# 03_-_MODULE_BLE.net
KiCad netlist of a schematic drawn in Altium Designer
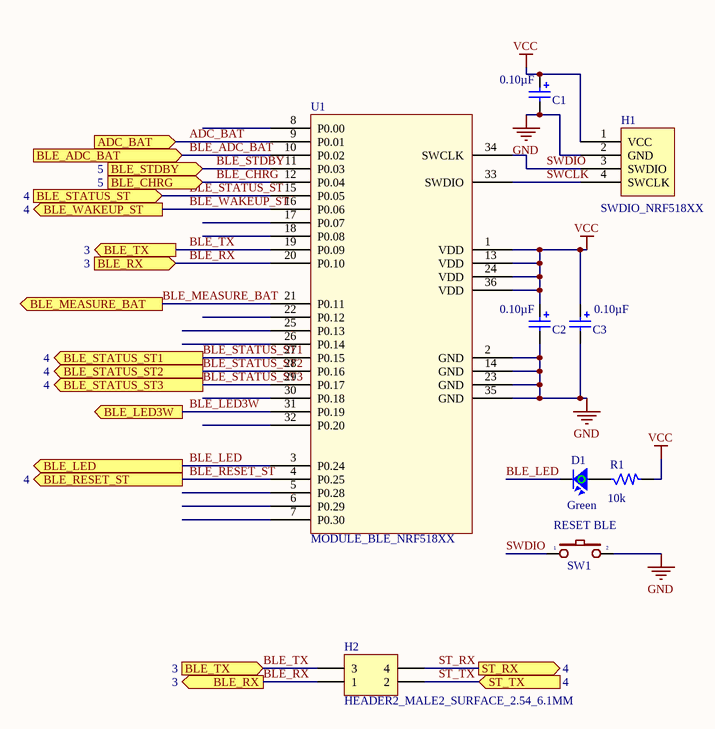
[diagram p0: [03] - MODULE BLE.SchDoc]

(export (version "E")
  (design (tool "Eeschema 10.0.6"))
  (components
    (comp (ref "C1")
      (value "C_104_0603_CERAMIC_16V")
      (footprint "CAP_SMD0603")
      (description "CAP CER 0.1UF 16V X7R 0603")
      (fields
        (field (name "MANUFACTURER") "Murata Electronics North America")
        (field (name "MANUFACTURER PART NUMBER") "GRM188R71C104KA01D")
        (field (name "CAPACITANCE") "0.10µF")
      )
      (libsource (lib "ALTIUM_LIB") (part "C_104_0603_CERAMIC_16V"))
    )
    (comp (ref "C2")
      (value "C_104_0603_CERAMIC_16V")
      (footprint "CAP_SMD0603")
      (description "CAP CER 0.1UF 16V X7R 0603")
      (fields
        (field (name "MANUFACTURER") "Murata Electronics North America")
        (field (name "MANUFACTURER PART NUMBER") "GRM188R71C104KA01D")
        (field (name "CAPACITANCE") "0.10µF")
      )
      (libsource (lib "ALTIUM_LIB") (part "C_104_0603_CERAMIC_16V"))
    )
    (comp (ref "C3")
      (value "C_104_0603_CERAMIC_16V")
      (footprint "CAP_SMD0603")
      (description "CAP CER 0.1UF 16V X7R 0603")
      (fields
        (field (name "MANUFACTURER") "Murata Electronics North America")
        (field (name "MANUFACTURER PART NUMBER") "GRM188R71C104KA01D")
        (field (name "CAPACITANCE") "0.10µF")
      )
      (libsource (lib "ALTIUM_LIB") (part "C_104_0603_CERAMIC_16V"))
    )
    (comp (ref "D1")
      (value "LED2_GREEN_0603_2V")
      (footprint "LED_GREEN_SMD0603")
      (description "LED GREEN CLEAR 0603 SMD")
      (fields
        (field (name "MANUFACTURER") "Lite-On Inc.")
        (field (name "MANUFACTURER PART NUMBER") "LTST-C191KGKT")
        (field (name "COLOR") "Green")
      )
      (libsource (lib "ALTIUM_LIB") (part "LED2_GREEN_0603_2V"))
    )
    (comp (ref "H1")
      (value "SWDIO_NRF518XX")
      (footprint "HEADER4_ISP_NRF518xx_SUR1.27")
      (description "CONN HEADER 4POS .100 STR TIN")
      (fields
        (field (name "MANUFACTURER") "Amphenol FCI")
        (field (name "MANUFACTURER PART NUMBER") "68002-404HLF")
      )
      (libsource (lib "ALTIUM_LIB") (part "HEADER4_ISP_NRF518XX_HOLE_2.54"))
    )
    (comp (ref "H2")
      (value "HEADER2_MALE2_SURFACE_2.54_6.1MM")
      (footprint "HEADER2_MALE2_SUR2.54")
      (description "CONN HEADER 4POS TIN SMD")
      (fields
        (field (name "MANUFACTURER") "Molex, LLC")
        (field (name "MANUFACTURER PART NUMBER") "0015912040")
      )
      (libsource (lib "SchematicLib") (part "HEADER2_MALE2_SURFACE_2.54_6.1MM"))
    )
    (comp (ref "R1")
      (value "R_10K_SMD0603_1%_1/10W")
      (footprint "RES_SMD0603")
      (description "RES SMD 10K OHM 1% 1/10W 0603")
      (fields
        (field (name "MANUFACTURER") "Yageo")
        (field (name "MANUFACTURER PART NUMBER") "RC0603FR-0710KL")
        (field (name "RESISTANCE (OHMS)") "10k")
      )
      (libsource (lib "ALTIUM_LIB") (part "R_10K_SMD0603_1%_1/10W"))
    )
    (comp (ref "SW1")
      (value "RESET BLE")
      (footprint "SW2-SMD")
      (description "SWITCH TACTILE SPST-NO 0.05A 12V")
      (fields
        (field (name "MANUFACTURER") "Wurth Electronics Inc")
        (field (name "MANUFACTURER PART NUMBER") "434121050836")
      )
      (libsource (lib "ALTIUM_LIB") (part "SW2_DPST_SURFACE_5MM"))
    )
    (comp (ref "U1")
      (value "MODULE_BLE_NRF518XX")
      (footprint "MODULE_NRF518xx")
      (libsource (lib "ALTIUM_LIB") (part "MODULE_BLE_NRF518XX"))
    )
  )
  (nets
    (net (code "1") (name "/ADC_BAT") (class "Default")
      (node (ref "U1") (pin "9") (pinfunction "P0.01_9") (pintype "passive"))
    )
    (net (code "2") (name "/BLE_ADC_BAT") (class "Default")
      (node (ref "U1") (pin "10") (pinfunction "P0.02_10") (pintype "passive"))
    )
    (net (code "3") (name "/BLE_CHRG") (class "Default")
      (node (ref "U1") (pin "12") (pinfunction "P0.04_12") (pintype "passive"))
    )
    (net (code "4") (name "/BLE_LED") (class "Default")
      (node (ref "D1") (pin "2") (pinfunction "2_2") (pintype "passive"))
      (node (ref "U1") (pin "3") (pinfunction "P0.24_3") (pintype "passive"))
    )
    (net (code "5") (name "/BLE_LED3W") (class "Default")
      (node (ref "U1") (pin "31") (pinfunction "P0.19_31") (pintype "passive"))
    )
    (net (code "6") (name "/BLE_MEASURE_BAT") (class "Default")
      (node (ref "U1") (pin "21") (pinfunction "P0.11_21") (pintype "passive"))
    )
    (net (code "7") (name "/BLE_RESET_ST") (class "Default")
      (node (ref "U1") (pin "4") (pinfunction "P0.25_4") (pintype "passive"))
    )
    (net (code "8") (name "/BLE_RX") (class "Default")
      (node (ref "H2") (pin "1") (pinfunction "1_1") (pintype "passive"))
      (node (ref "U1") (pin "20") (pinfunction "P0.10_20") (pintype "passive"))
    )
    (net (code "9") (name "/BLE_STATUS_ST") (class "Default")
      (node (ref "U1") (pin "15") (pinfunction "P0.05_15") (pintype "passive"))
    )
    (net (code "10") (name "/BLE_STATUS_ST1") (class "Default")
      (node (ref "U1") (pin "27") (pinfunction "P0.15_27") (pintype "passive"))
    )
    (net (code "11") (name "/BLE_STATUS_ST2") (class "Default")
      (node (ref "U1") (pin "28") (pinfunction "P0.16_28") (pintype "passive"))
    )
    (net (code "12") (name "/BLE_STATUS_ST3") (class "Default")
      (node (ref "U1") (pin "29") (pinfunction "P0.17_29") (pintype "passive"))
    )
    (net (code "13") (name "/BLE_STDBY") (class "Default")
      (node (ref "U1") (pin "11") (pinfunction "P0.03_11") (pintype "passive"))
    )
    (net (code "14") (name "/BLE_TX") (class "Default")
      (node (ref "H2") (pin "3") (pinfunction "3_3") (pintype "passive"))
      (node (ref "U1") (pin "19") (pinfunction "P0.09_19") (pintype "passive"))
    )
    (net (code "15") (name "/BLE_WAKEUP_ST") (class "Default")
      (node (ref "U1") (pin "16") (pinfunction "P0.06_16") (pintype "passive"))
    )
    (net (code "16") (name "/ST_RX") (class "Default")
      (node (ref "H2") (pin "4") (pinfunction "4_4") (pintype "passive"))
    )
    (net (code "17") (name "/ST_TX") (class "Default")
      (node (ref "H2") (pin "2") (pinfunction "2_2") (pintype "passive"))
    )
    (net (code "18") (name "/SWCLK") (class "Default")
      (node (ref "H1") (pin "4") (pinfunction "SWCLK_4") (pintype "passive"))
      (node (ref "U1") (pin "33") (pinfunction "SWDIO_33") (pintype "passive"))
    )
    (net (code "19") (name "/SWDIO") (class "Default")
      (node (ref "H1") (pin "3") (pinfunction "SWDIO_3") (pintype "passive"))
      (node (ref "SW1") (pin "1") (pinfunction "1_1") (pintype "passive"))
      (node (ref "U1") (pin "34") (pinfunction "SWCLK_34") (pintype "passive"))
    )
    (net (code "20") (name "GND") (class "Default")
      (node (ref "C1") (pin "2") (pinfunction "2_2") (pintype "passive"))
      (node (ref "C2") (pin "2") (pinfunction "2_2") (pintype "passive"))
      (node (ref "C3") (pin "2") (pinfunction "2_2") (pintype "passive"))
      (node (ref "H1") (pin "2") (pinfunction "GND_2") (pintype "passive"))
      (node (ref "SW1") (pin "2") (pinfunction "2_2") (pintype "passive"))
      (node (ref "U1") (pin "14") (pinfunction "GND_14") (pintype "passive"))
      (node (ref "U1") (pin "2") (pinfunction "GND_2") (pintype "passive"))
      (node (ref "U1") (pin "23") (pinfunction "GND_23") (pintype "passive"))
      (node (ref "U1") (pin "35") (pinfunction "GND_35") (pintype "passive"))
    )
    (net (code "21") (name "Net-(D1-Pad1)") (class "Default")
      (node (ref "D1") (pin "1") (pinfunction "1_1") (pintype "passive"))
      (node (ref "R1") (pin "1") (pinfunction "1_1") (pintype "passive"))
    )
    (net (code "22") (name "VCC") (class "Default")
      (node (ref "C1") (pin "1") (pinfunction "1_1") (pintype "passive"))
      (node (ref "C2") (pin "1") (pinfunction "1_1") (pintype "passive"))
      (node (ref "C3") (pin "1") (pinfunction "1_1") (pintype "passive"))
      (node (ref "H1") (pin "1") (pinfunction "VCC_1") (pintype "passive"))
      (node (ref "R1") (pin "2") (pinfunction "2_2") (pintype "passive"))
      (node (ref "U1") (pin "1") (pinfunction "VDD_1") (pintype "passive"))
      (node (ref "U1") (pin "13") (pinfunction "VDD_13") (pintype "passive"))
      (node (ref "U1") (pin "24") (pinfunction "VDD_24") (pintype "passive"))
      (node (ref "U1") (pin "36") (pinfunction "VDD_36") (pintype "passive"))
    )
    (net (code "23") (name "unconnected-(U1-P0.00-Pad8)") (class "Default")
      (node (ref "U1") (pin "8") (pinfunction "P0.00_8") (pintype "passive"))
    )
    (net (code "24") (name "unconnected-(U1-P0.07-Pad17)") (class "Default")
      (node (ref "U1") (pin "17") (pinfunction "P0.07_17") (pintype "passive"))
    )
    (net (code "25") (name "unconnected-(U1-P0.08-Pad18)") (class "Default")
      (node (ref "U1") (pin "18") (pinfunction "P0.08_18") (pintype "passive"))
    )
    (net (code "26") (name "unconnected-(U1-P0.12-Pad22)") (class "Default")
      (node (ref "U1") (pin "22") (pinfunction "P0.12_22") (pintype "passive"))
    )
    (net (code "27") (name "unconnected-(U1-P0.13-Pad25)") (class "Default")
      (node (ref "U1") (pin "25") (pinfunction "P0.13_25") (pintype "passive"))
    )
    (net (code "28") (name "unconnected-(U1-P0.14-Pad26)") (class "Default")
      (node (ref "U1") (pin "26") (pinfunction "P0.14_26") (pintype "passive"))
    )
    (net (code "29") (name "unconnected-(U1-P0.18-Pad30)") (class "Default")
      (node (ref "U1") (pin "30") (pinfunction "P0.18_30") (pintype "passive"))
    )
    (net (code "30") (name "unconnected-(U1-P0.20-Pad32)") (class "Default")
      (node (ref "U1") (pin "32") (pinfunction "P0.20_32") (pintype "passive"))
    )
    (net (code "31") (name "unconnected-(U1-P0.28-Pad5)") (class "Default")
      (node (ref "U1") (pin "5") (pinfunction "P0.28_5") (pintype "passive"))
    )
    (net (code "32") (name "unconnected-(U1-P0.29-Pad6)") (class "Default")
      (node (ref "U1") (pin "6") (pinfunction "P0.29_6") (pintype "passive"))
    )
    (net (code "33") (name "unconnected-(U1-P0.30-Pad7)") (class "Default")
      (node (ref "U1") (pin "7") (pinfunction "P0.30_7") (pintype "passive"))
    )
  )
)
